# Tube_board_v2_1.net
KiCad netlist of a schematic drawn in EAGLE
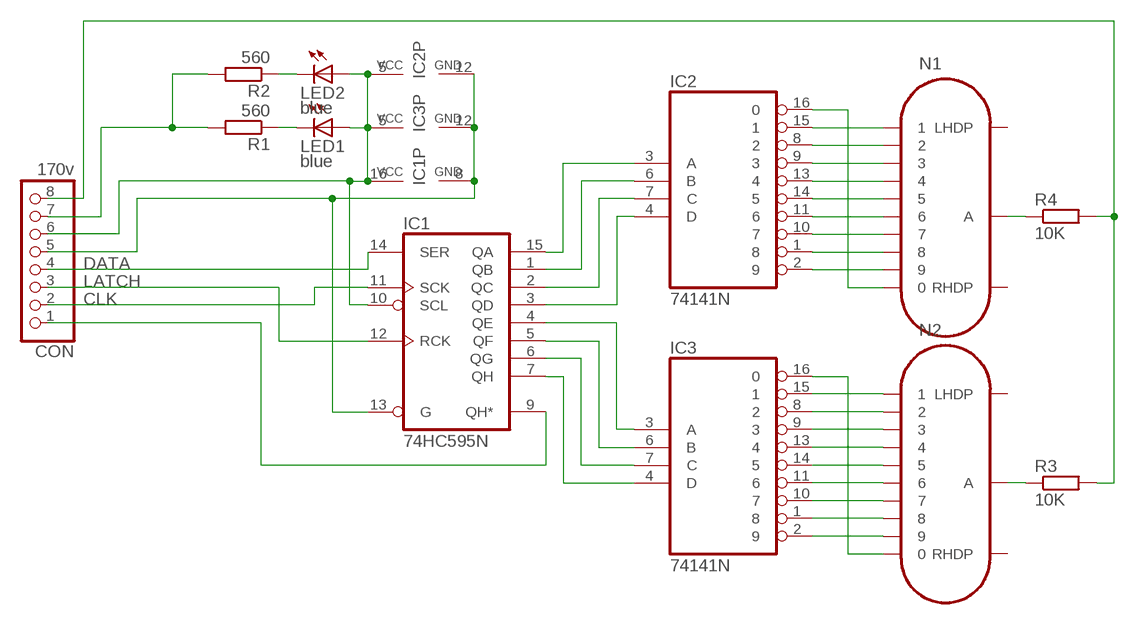
[diagram p0: schematic, sheet 1]

(export (version "E")
  (design (tool "Eeschema 10.0.6"))
  (components
    (comp (ref "CON")
      (value "170v")
      (footprint "eagle-import:1X08")
      (libsource (lib "eagle-import") (part "PINHD-1X8"))
    )
    (comp (ref "IC1")
      (value "74HC595N")
      (footprint "eagle-import:DIL16")
      (libsource (lib "eagle-import") (part "74595NHC"))
    )
    (comp (ref "IC2")
      (value "74141N")
      (footprint "eagle-import:DIL16")
      (libsource (lib "eagle-import") (part "74141N"))
    )
    (comp (ref "IC3")
      (value "74141N")
      (footprint "eagle-import:DIL16")
      (libsource (lib "eagle-import") (part "74141N"))
    )
    (comp (ref "LED1")
      (value "blue")
      (footprint "eagle-import:LED3MM")
      (libsource (lib "eagle-import") (part "LED3MM"))
    )
    (comp (ref "LED2")
      (value "blue")
      (footprint "eagle-import:LED3MM")
      (libsource (lib "eagle-import") (part "LED3MM"))
    )
    (comp (ref "N1")
      (value "IN-14")
      (footprint "eagle-import:IN-14")
      (libsource (lib "eagle-import") (part "IN-14"))
    )
    (comp (ref "N2")
      (value "IN-14")
      (footprint "eagle-import:IN-14")
      (libsource (lib "eagle-import") (part "IN-14"))
    )
    (comp (ref "R1")
      (value "560")
      (footprint "eagle-import:0204_7")
      (libsource (lib "eagle-import") (part "R-EU_0204/7"))
    )
    (comp (ref "R2")
      (value "560")
      (footprint "eagle-import:0204_7")
      (libsource (lib "eagle-import") (part "R-EU_0204/7"))
    )
    (comp (ref "R3")
      (value "10K")
      (footprint "eagle-import:0204_7")
      (libsource (lib "eagle-import") (part "R-EU_0204/7"))
    )
    (comp (ref "R4")
      (value "10K")
      (footprint "eagle-import:0204_7")
      (libsource (lib "eagle-import") (part "R-EU_0204/7"))
    )
  )
  (nets
    (net (code "1") (name "/CLK") (class "Default")
      (node (ref "CON") (pin "2") (pinfunction "2_2") (pintype "passive"))
      (node (ref "IC1") (pin "11") (pinfunction "SCK_11") (pintype "input"))
    )
    (net (code "2") (name "/DATA") (class "Default")
      (node (ref "CON") (pin "4") (pinfunction "4_4") (pintype "passive"))
      (node (ref "IC1") (pin "14") (pinfunction "SER_14") (pintype "input"))
    )
    (net (code "3") (name "/LATCH") (class "Default")
      (node (ref "CON") (pin "3") (pinfunction "3_3") (pintype "passive"))
      (node (ref "IC1") (pin "12") (pinfunction "RCK_12") (pintype "input"))
    )
    (net (code "4") (name "Net-(CON-Pad7)") (class "Default")
      (node (ref "CON") (pin "7") (pinfunction "7_7") (pintype "passive"))
      (node (ref "R1") (pin "2") (pinfunction "2_2") (pintype "passive"))
      (node (ref "R2") (pin "2") (pinfunction "2_2") (pintype "passive"))
    )
    (net (code "5") (name "Net-(CON-Pad8)") (class "Default")
      (node (ref "CON") (pin "8") (pinfunction "8_8") (pintype "passive"))
      (node (ref "R3") (pin "2") (pinfunction "2_2") (pintype "passive"))
      (node (ref "R4") (pin "2") (pinfunction "2_2") (pintype "passive"))
    )
    (net (code "6") (name "Net-(IC1A-G)") (class "Default")
      (node (ref "CON") (pin "5") (pinfunction "5_5") (pintype "passive"))
      (node (ref "IC1") (pin "13") (pinfunction "G_13") (pintype "input"))
      (node (ref "IC1") (pin "8") (pinfunction "GND_8") (pintype "power_in"))
      (node (ref "IC2") (pin "12") (pinfunction "GND_12") (pintype "power_in"))
      (node (ref "IC3") (pin "12") (pinfunction "GND_12") (pintype "power_in"))
    )
    (net (code "7") (name "Net-(IC1A-QA)") (class "Default")
      (node (ref "IC1") (pin "15") (pinfunction "QA_15") (pintype "tri_state"))
      (node (ref "IC2") (pin "3") (pinfunction "A_3") (pintype "input"))
    )
    (net (code "8") (name "Net-(IC1A-QB)") (class "Default")
      (node (ref "IC1") (pin "1") (pinfunction "QB_1") (pintype "tri_state"))
      (node (ref "IC2") (pin "6") (pinfunction "B_6") (pintype "input"))
    )
    (net (code "9") (name "Net-(IC1A-QC)") (class "Default")
      (node (ref "IC1") (pin "2") (pinfunction "QC_2") (pintype "tri_state"))
      (node (ref "IC2") (pin "7") (pinfunction "C_7") (pintype "input"))
    )
    (net (code "10") (name "Net-(IC1A-QD)") (class "Default")
      (node (ref "IC1") (pin "3") (pinfunction "QD_3") (pintype "tri_state"))
      (node (ref "IC2") (pin "4") (pinfunction "D_4") (pintype "input"))
    )
    (net (code "11") (name "Net-(IC1A-QE)") (class "Default")
      (node (ref "IC1") (pin "4") (pinfunction "QE_4") (pintype "tri_state"))
      (node (ref "IC3") (pin "3") (pinfunction "A_3") (pintype "input"))
    )
    (net (code "12") (name "Net-(IC1A-QF)") (class "Default")
      (node (ref "IC1") (pin "5") (pinfunction "QF_5") (pintype "tri_state"))
      (node (ref "IC3") (pin "6") (pinfunction "B_6") (pintype "input"))
    )
    (net (code "13") (name "Net-(IC1A-QG)") (class "Default")
      (node (ref "IC1") (pin "6") (pinfunction "QG_6") (pintype "tri_state"))
      (node (ref "IC3") (pin "7") (pinfunction "C_7") (pintype "input"))
    )
    (net (code "14") (name "Net-(IC1A-QH)") (class "Default")
      (node (ref "IC1") (pin "7") (pinfunction "QH_7") (pintype "tri_state"))
      (node (ref "IC3") (pin "4") (pinfunction "D_4") (pintype "input"))
    )
    (net (code "15") (name "Net-(IC1A-QH*)") (class "Default")
      (node (ref "CON") (pin "1") (pinfunction "1_1") (pintype "passive"))
      (node (ref "IC1") (pin "9") (pinfunction "QH*_9") (pintype "tri_state"))
    )
    (net (code "16") (name "Net-(IC1A-SCL)") (class "Default")
      (node (ref "CON") (pin "6") (pinfunction "6_6") (pintype "passive"))
      (node (ref "IC1") (pin "10") (pinfunction "SCL_10") (pintype "input"))
      (node (ref "IC1") (pin "16") (pinfunction "VCC_16") (pintype "power_in"))
      (node (ref "IC2") (pin "5") (pinfunction "VCC_5") (pintype "power_in"))
      (node (ref "IC3") (pin "5") (pinfunction "VCC_5") (pintype "power_in"))
      (node (ref "LED1") (pin "A") (pinfunction "A_A") (pintype "passive"))
      (node (ref "LED2") (pin "A") (pinfunction "A_A") (pintype "passive"))
    )
    (net (code "17") (name "Net-(IC2A-0)") (class "Default")
      (node (ref "IC2") (pin "16") (pinfunction "0_16") (pintype "open_collector"))
      (node (ref "N1") (pin "0") (pinfunction "0_0") (pintype "bidirectional"))
    )
    (net (code "18") (name "Net-(IC2A-1)") (class "Default")
      (node (ref "IC2") (pin "15") (pinfunction "1_15") (pintype "open_collector"))
      (node (ref "N1") (pin "1") (pinfunction "1_1") (pintype "bidirectional"))
    )
    (net (code "19") (name "Net-(IC2A-2)") (class "Default")
      (node (ref "IC2") (pin "8") (pinfunction "2_8") (pintype "open_collector"))
      (node (ref "N1") (pin "2") (pinfunction "2_2") (pintype "bidirectional"))
    )
    (net (code "20") (name "Net-(IC2A-3)") (class "Default")
      (node (ref "IC2") (pin "9") (pinfunction "3_9") (pintype "open_collector"))
      (node (ref "N1") (pin "3") (pinfunction "3_3") (pintype "bidirectional"))
    )
    (net (code "21") (name "Net-(IC2A-4)") (class "Default")
      (node (ref "IC2") (pin "13") (pinfunction "4_13") (pintype "open_collector"))
      (node (ref "N1") (pin "4") (pinfunction "4_4") (pintype "bidirectional"))
    )
    (net (code "22") (name "Net-(IC2A-5)") (class "Default")
      (node (ref "IC2") (pin "14") (pinfunction "5_14") (pintype "open_collector"))
      (node (ref "N1") (pin "5") (pinfunction "5_5") (pintype "bidirectional"))
    )
    (net (code "23") (name "Net-(IC2A-6)") (class "Default")
      (node (ref "IC2") (pin "11") (pinfunction "6_11") (pintype "open_collector"))
      (node (ref "N1") (pin "6") (pinfunction "6_6") (pintype "bidirectional"))
    )
    (net (code "24") (name "Net-(IC2A-7)") (class "Default")
      (node (ref "IC2") (pin "10") (pinfunction "7_10") (pintype "open_collector"))
      (node (ref "N1") (pin "7") (pinfunction "7_7") (pintype "bidirectional"))
    )
    (net (code "25") (name "Net-(IC2A-8)") (class "Default")
      (node (ref "IC2") (pin "1") (pinfunction "8_1") (pintype "open_collector"))
      (node (ref "N1") (pin "8") (pinfunction "8_8") (pintype "bidirectional"))
    )
    (net (code "26") (name "Net-(IC2A-9)") (class "Default")
      (node (ref "IC2") (pin "2") (pinfunction "9_2") (pintype "open_collector"))
      (node (ref "N1") (pin "9") (pinfunction "9_9") (pintype "bidirectional"))
    )
    (net (code "27") (name "Net-(IC3A-0)") (class "Default")
      (node (ref "IC3") (pin "16") (pinfunction "0_16") (pintype "open_collector"))
      (node (ref "N2") (pin "0") (pinfunction "0_0") (pintype "bidirectional"))
    )
    (net (code "28") (name "Net-(IC3A-1)") (class "Default")
      (node (ref "IC3") (pin "15") (pinfunction "1_15") (pintype "open_collector"))
      (node (ref "N2") (pin "1") (pinfunction "1_1") (pintype "bidirectional"))
    )
    (net (code "29") (name "Net-(IC3A-2)") (class "Default")
      (node (ref "IC3") (pin "8") (pinfunction "2_8") (pintype "open_collector"))
      (node (ref "N2") (pin "2") (pinfunction "2_2") (pintype "bidirectional"))
    )
    (net (code "30") (name "Net-(IC3A-3)") (class "Default")
      (node (ref "IC3") (pin "9") (pinfunction "3_9") (pintype "open_collector"))
      (node (ref "N2") (pin "3") (pinfunction "3_3") (pintype "bidirectional"))
    )
    (net (code "31") (name "Net-(IC3A-4)") (class "Default")
      (node (ref "IC3") (pin "13") (pinfunction "4_13") (pintype "open_collector"))
      (node (ref "N2") (pin "4") (pinfunction "4_4") (pintype "bidirectional"))
    )
    (net (code "32") (name "Net-(IC3A-5)") (class "Default")
      (node (ref "IC3") (pin "14") (pinfunction "5_14") (pintype "open_collector"))
      (node (ref "N2") (pin "5") (pinfunction "5_5") (pintype "bidirectional"))
    )
    (net (code "33") (name "Net-(IC3A-6)") (class "Default")
      (node (ref "IC3") (pin "11") (pinfunction "6_11") (pintype "open_collector"))
      (node (ref "N2") (pin "6") (pinfunction "6_6") (pintype "bidirectional"))
    )
    (net (code "34") (name "Net-(IC3A-7)") (class "Default")
      (node (ref "IC3") (pin "10") (pinfunction "7_10") (pintype "open_collector"))
      (node (ref "N2") (pin "7") (pinfunction "7_7") (pintype "bidirectional"))
    )
    (net (code "35") (name "Net-(IC3A-8)") (class "Default")
      (node (ref "IC3") (pin "1") (pinfunction "8_1") (pintype "open_collector"))
      (node (ref "N2") (pin "8") (pinfunction "8_8") (pintype "bidirectional"))
    )
    (net (code "36") (name "Net-(IC3A-9)") (class "Default")
      (node (ref "IC3") (pin "2") (pinfunction "9_2") (pintype "open_collector"))
      (node (ref "N2") (pin "9") (pinfunction "9_9") (pintype "bidirectional"))
    )
    (net (code "37") (name "Net-(LED1-C)") (class "Default")
      (node (ref "LED1") (pin "K") (pinfunction "C_K") (pintype "passive"))
      (node (ref "R1") (pin "1") (pinfunction "1_1") (pintype "passive"))
    )
    (net (code "38") (name "Net-(LED2-C)") (class "Default")
      (node (ref "LED2") (pin "K") (pinfunction "C_K") (pintype "passive"))
      (node (ref "R2") (pin "1") (pinfunction "1_1") (pintype "passive"))
    )
    (net (code "39") (name "Net-(N1-PadA)") (class "Default")
      (node (ref "N1") (pin "A") (pinfunction "A_A") (pintype "bidirectional"))
      (node (ref "R4") (pin "1") (pinfunction "1_1") (pintype "passive"))
    )
    (net (code "40") (name "Net-(N2-PadA)") (class "Default")
      (node (ref "N2") (pin "A") (pinfunction "A_A") (pintype "bidirectional"))
      (node (ref "R3") (pin "1") (pinfunction "1_1") (pintype "passive"))
    )
    (net (code "41") (name "unconnected-(N1-PadLHDP)") (class "Default")
      (node (ref "N1") (pin "LHDP") (pinfunction "LHDP_LHDP") (pintype "bidirectional"))
    )
    (net (code "42") (name "unconnected-(N1-PadRHDP)") (class "Default")
      (node (ref "N1") (pin "RHDP") (pinfunction "RHDP_RHDP") (pintype "bidirectional"))
    )
    (net (code "43") (name "unconnected-(N2-PadLHDP)") (class "Default")
      (node (ref "N2") (pin "LHDP") (pinfunction "LHDP_LHDP") (pintype "bidirectional"))
    )
    (net (code "44") (name "unconnected-(N2-PadRHDP)") (class "Default")
      (node (ref "N2") (pin "RHDP") (pinfunction "RHDP_RHDP") (pintype "bidirectional"))
    )
  )
)
